# Design_Schematic.net
KiCad netlist of a schematic drawn in EAGLE
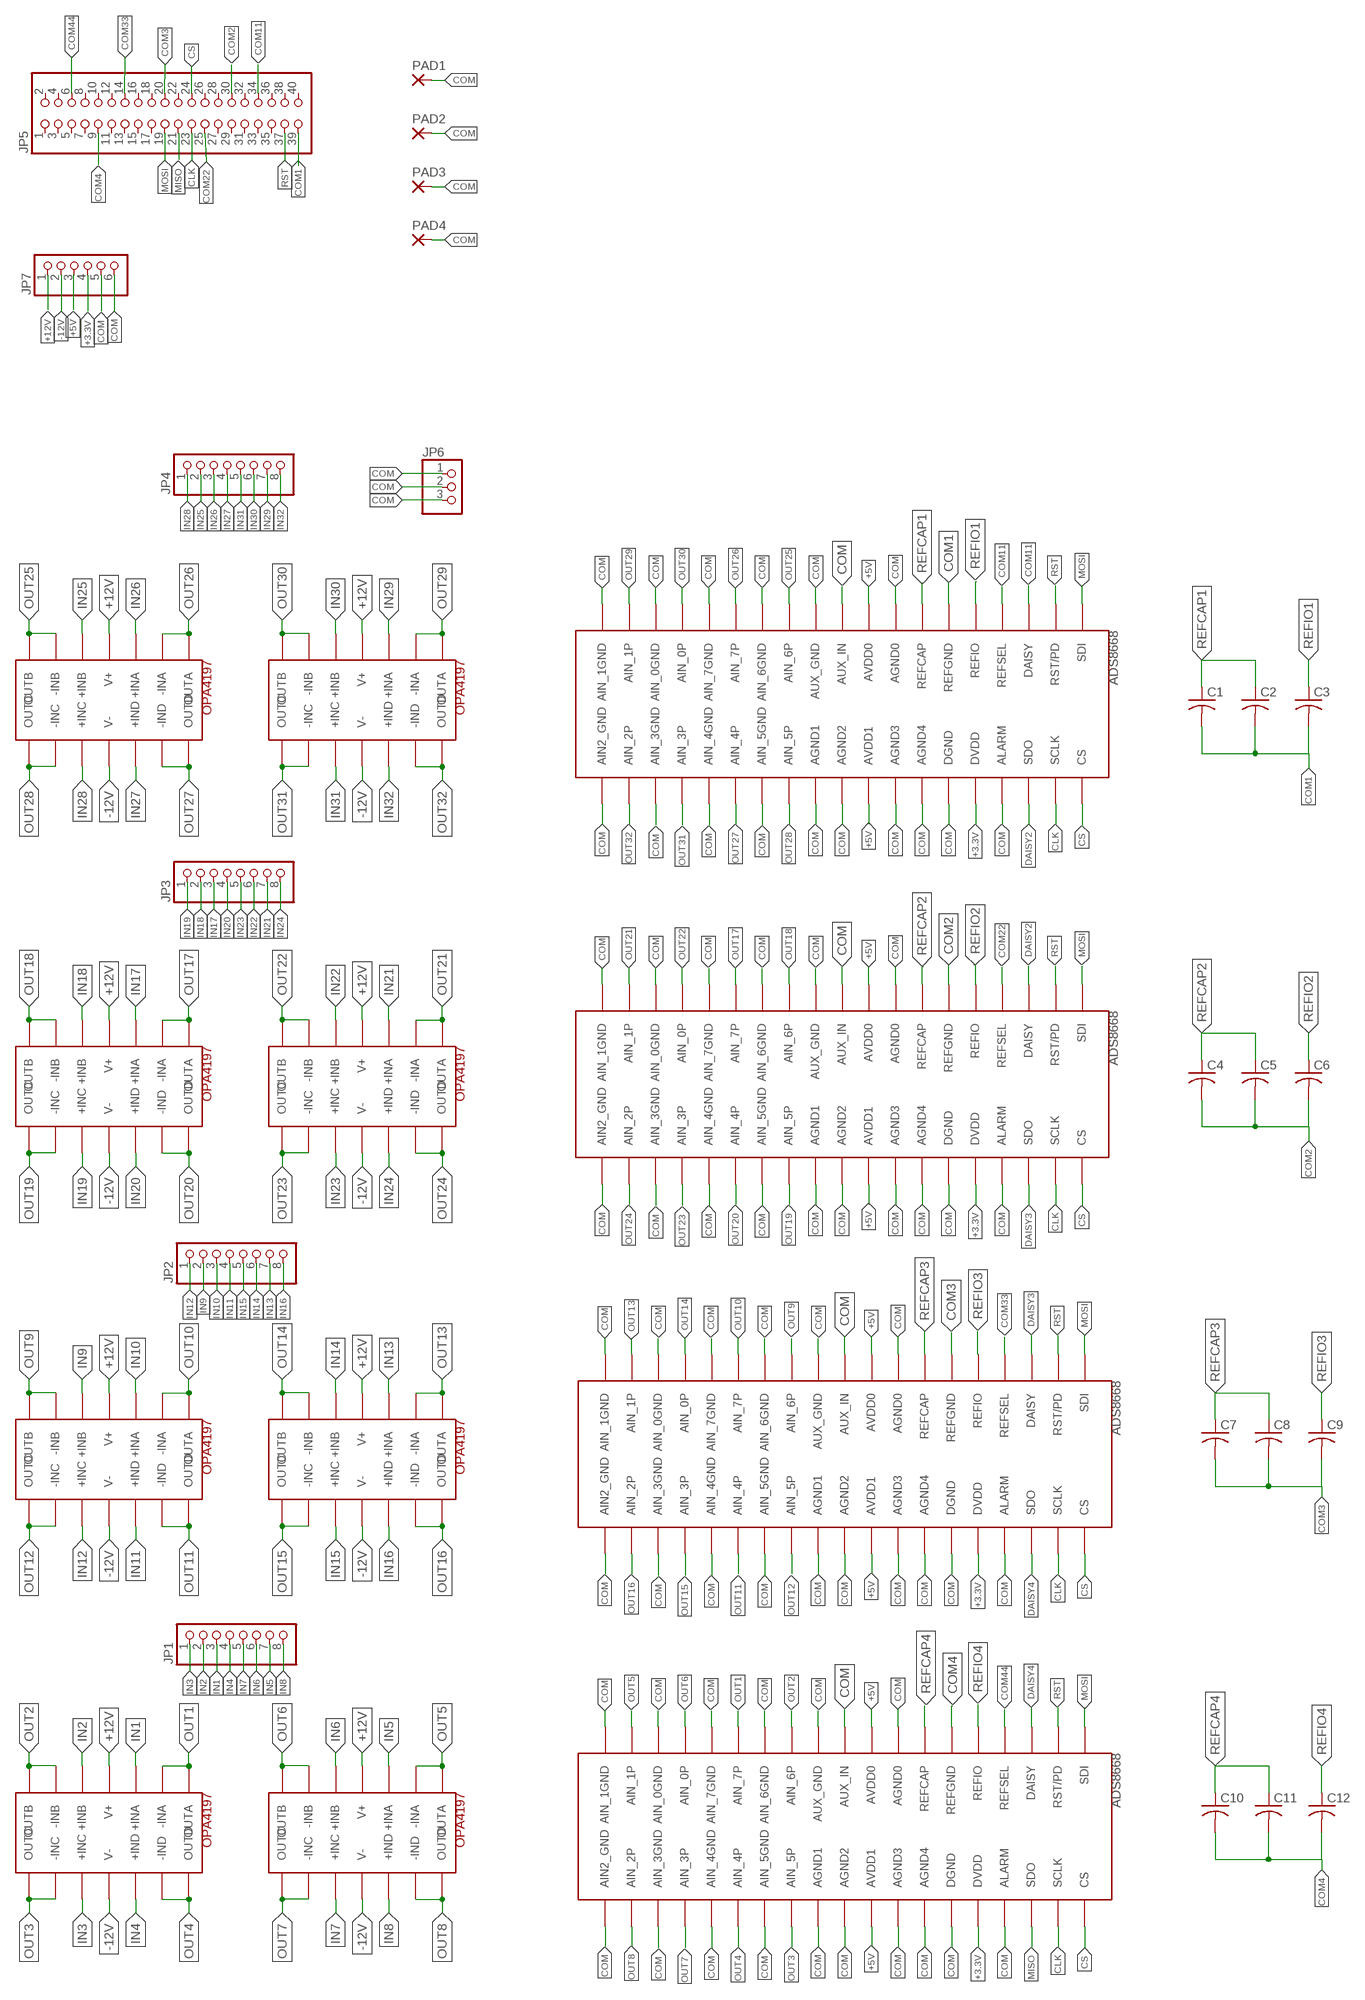
[diagram p0: schematic, sheet 1]

(export (version "E")
  (design (tool "Eeschema 10.0.6"))
  (components
    (comp (ref "ADC1")
      (value "ADS8668")
      (footprint "eagle-import:ADS8668")
      (libsource (lib "eagle-import") (part "ADS8668"))
    )
    (comp (ref "ADC2")
      (value "ADS8668")
      (footprint "eagle-import:ADS8668")
      (libsource (lib "eagle-import") (part "ADS8668"))
    )
    (comp (ref "ADC3")
      (value "ADS8668")
      (footprint "eagle-import:ADS8668")
      (libsource (lib "eagle-import") (part "ADS8668"))
    )
    (comp (ref "ADC4")
      (value "ADS8668")
      (footprint "eagle-import:ADS8668")
      (libsource (lib "eagle-import") (part "ADS8668"))
    )
    (comp (ref "C1")
      (value "C-US025-030X050")
      (footprint "eagle-import:C025-030X050")
      (libsource (lib "eagle-import") (part "C-US025-030X050"))
    )
    (comp (ref "C2")
      (value "C-US025-030X050")
      (footprint "eagle-import:C025-030X050")
      (libsource (lib "eagle-import") (part "C-US025-030X050"))
    )
    (comp (ref "C3")
      (value "C-US025-030X050")
      (footprint "eagle-import:C025-030X050")
      (libsource (lib "eagle-import") (part "C-US025-030X050"))
    )
    (comp (ref "C4")
      (value "C-US025-030X050")
      (footprint "eagle-import:C025-030X050")
      (libsource (lib "eagle-import") (part "C-US025-030X050"))
    )
    (comp (ref "C5")
      (value "C-US025-030X050")
      (footprint "eagle-import:C025-030X050")
      (libsource (lib "eagle-import") (part "C-US025-030X050"))
    )
    (comp (ref "C6")
      (value "C-US025-030X050")
      (footprint "eagle-import:C025-030X050")
      (libsource (lib "eagle-import") (part "C-US025-030X050"))
    )
    (comp (ref "C7")
      (value "C-US025-030X050")
      (footprint "eagle-import:C025-030X050")
      (libsource (lib "eagle-import") (part "C-US025-030X050"))
    )
    (comp (ref "C8")
      (value "C-US025-030X050")
      (footprint "eagle-import:C025-030X050")
      (libsource (lib "eagle-import") (part "C-US025-030X050"))
    )
    (comp (ref "C9")
      (value "C-US025-030X050")
      (footprint "eagle-import:C025-030X050")
      (libsource (lib "eagle-import") (part "C-US025-030X050"))
    )
    (comp (ref "C10")
      (value "C-US025-030X050")
      (footprint "eagle-import:C025-030X050")
      (libsource (lib "eagle-import") (part "C-US025-030X050"))
    )
    (comp (ref "C11")
      (value "C-US025-030X050")
      (footprint "eagle-import:C025-030X050")
      (libsource (lib "eagle-import") (part "C-US025-030X050"))
    )
    (comp (ref "C12")
      (value "C-US025-030X050")
      (footprint "eagle-import:C025-030X050")
      (libsource (lib "eagle-import") (part "C-US025-030X050"))
    )
    (comp (ref "JP1")
      (value "PINHD-1X8CLEANBIG")
      (footprint "eagle-import:1X08-CLEANBIG")
      (libsource (lib "eagle-import") (part "PINHD-1X8CLEANBIG"))
    )
    (comp (ref "JP2")
      (value "PINHD-1X8CLEANBIG")
      (footprint "eagle-import:1X08-CLEANBIG")
      (libsource (lib "eagle-import") (part "PINHD-1X8CLEANBIG"))
    )
    (comp (ref "JP3")
      (value "PINHD-1X8CLEANBIG")
      (footprint "eagle-import:1X08-CLEANBIG")
      (libsource (lib "eagle-import") (part "PINHD-1X8CLEANBIG"))
    )
    (comp (ref "JP4")
      (value "PINHD-1X8CLEANBIG")
      (footprint "eagle-import:1X08-CLEANBIG")
      (libsource (lib "eagle-import") (part "PINHD-1X8CLEANBIG"))
    )
    (comp (ref "JP5")
      (value "PINHD-2X20")
      (footprint "eagle-import:2X20")
      (libsource (lib "eagle-import") (part "PINHD-2X20"))
    )
    (comp (ref "JP6")
      (value "PINHD-1X3")
      (footprint "eagle-import:1X03")
      (libsource (lib "eagle-import") (part "PINHD-1X3"))
    )
    (comp (ref "JP7")
      (value "PINHD-1X6")
      (footprint "eagle-import:1X06")
      (libsource (lib "eagle-import") (part "PINHD-1X6"))
    )
    (comp (ref "PAD1")
      (value "3,17/1,3")
      (footprint "eagle-import:3,17_1,3")
      (libsource (lib "eagle-import") (part "3,17/1,3"))
    )
    (comp (ref "PAD2")
      (value "3,17/1,3")
      (footprint "eagle-import:3,17_1,3")
      (libsource (lib "eagle-import") (part "3,17/1,3"))
    )
    (comp (ref "PAD3")
      (value "3,17/1,3")
      (footprint "eagle-import:3,17_1,3")
      (libsource (lib "eagle-import") (part "3,17/1,3"))
    )
    (comp (ref "PAD4")
      (value "3,17/1,3")
      (footprint "eagle-import:3,17_1,3")
      (libsource (lib "eagle-import") (part "3,17/1,3"))
    )
    (comp (ref "U$1")
      (value "OPA4197")
      (footprint "eagle-import:OPA4197")
      (libsource (lib "eagle-import") (part "OPA4197"))
    )
    (comp (ref "U$2")
      (value "OPA4197")
      (footprint "eagle-import:OPA4197")
      (libsource (lib "eagle-import") (part "OPA4197"))
    )
    (comp (ref "U$3")
      (value "OPA4197")
      (footprint "eagle-import:OPA4197")
      (libsource (lib "eagle-import") (part "OPA4197"))
    )
    (comp (ref "U$4")
      (value "OPA4197")
      (footprint "eagle-import:OPA4197")
      (libsource (lib "eagle-import") (part "OPA4197"))
    )
    (comp (ref "U$5")
      (value "OPA4197")
      (footprint "eagle-import:OPA4197")
      (libsource (lib "eagle-import") (part "OPA4197"))
    )
    (comp (ref "U$6")
      (value "OPA4197")
      (footprint "eagle-import:OPA4197")
      (libsource (lib "eagle-import") (part "OPA4197"))
    )
    (comp (ref "U$7")
      (value "OPA4197")
      (footprint "eagle-import:OPA4197")
      (libsource (lib "eagle-import") (part "OPA4197"))
    )
    (comp (ref "U$8")
      (value "OPA4197")
      (footprint "eagle-import:OPA4197")
      (libsource (lib "eagle-import") (part "OPA4197"))
    )
  )
  (nets
    (net (code "1") (name "+3.3V") (class "Default")
      (node (ref "ADC1") (pin "DVDD") (pinfunction "DVDD_DVDD") (pintype "bidirectional"))
      (node (ref "ADC2") (pin "DVDD") (pinfunction "DVDD_DVDD") (pintype "bidirectional"))
      (node (ref "ADC3") (pin "DVDD") (pinfunction "DVDD_DVDD") (pintype "bidirectional"))
      (node (ref "ADC4") (pin "DVDD") (pinfunction "DVDD_DVDD") (pintype "bidirectional"))
      (node (ref "JP7") (pin "4") (pinfunction "4_4") (pintype "passive"))
    )
    (net (code "2") (name "+5V") (class "Default")
      (node (ref "ADC1") (pin "AVDD0") (pinfunction "AVDD0_AVDD0") (pintype "bidirectional"))
      (node (ref "ADC1") (pin "AVDD1") (pinfunction "AVDD1_AVDD1") (pintype "bidirectional"))
      (node (ref "ADC2") (pin "AVDD0") (pinfunction "AVDD0_AVDD0") (pintype "bidirectional"))
      (node (ref "ADC2") (pin "AVDD1") (pinfunction "AVDD1_AVDD1") (pintype "bidirectional"))
      (node (ref "ADC3") (pin "AVDD0") (pinfunction "AVDD0_AVDD0") (pintype "bidirectional"))
      (node (ref "ADC3") (pin "AVDD1") (pinfunction "AVDD1_AVDD1") (pintype "bidirectional"))
      (node (ref "ADC4") (pin "AVDD0") (pinfunction "AVDD0_AVDD0") (pintype "bidirectional"))
      (node (ref "ADC4") (pin "AVDD1") (pinfunction "AVDD1_AVDD1") (pintype "bidirectional"))
      (node (ref "JP7") (pin "3") (pinfunction "3_3") (pintype "passive"))
    )
    (net (code "3") (name "+12V") (class "Default")
      (node (ref "JP7") (pin "1") (pinfunction "1_1") (pintype "passive"))
      (node (ref "U$1") (pin "V+") (pinfunction "V+_V+") (pintype "bidirectional"))
      (node (ref "U$2") (pin "V+") (pinfunction "V+_V+") (pintype "bidirectional"))
      (node (ref "U$3") (pin "V+") (pinfunction "V+_V+") (pintype "bidirectional"))
      (node (ref "U$4") (pin "V+") (pinfunction "V+_V+") (pintype "bidirectional"))
      (node (ref "U$5") (pin "V+") (pinfunction "V+_V+") (pintype "bidirectional"))
      (node (ref "U$6") (pin "V+") (pinfunction "V+_V+") (pintype "bidirectional"))
      (node (ref "U$7") (pin "V+") (pinfunction "V+_V+") (pintype "bidirectional"))
      (node (ref "U$8") (pin "V+") (pinfunction "V+_V+") (pintype "bidirectional"))
    )
    (net (code "4") (name "-12V") (class "Default")
      (node (ref "JP7") (pin "2") (pinfunction "2_2") (pintype "passive"))
      (node (ref "U$1") (pin "V-") (pinfunction "V-_V-") (pintype "bidirectional"))
      (node (ref "U$2") (pin "V-") (pinfunction "V-_V-") (pintype "bidirectional"))
      (node (ref "U$3") (pin "V-") (pinfunction "V-_V-") (pintype "bidirectional"))
      (node (ref "U$4") (pin "V-") (pinfunction "V-_V-") (pintype "bidirectional"))
      (node (ref "U$5") (pin "V-") (pinfunction "V-_V-") (pintype "bidirectional"))
      (node (ref "U$6") (pin "V-") (pinfunction "V-_V-") (pintype "bidirectional"))
      (node (ref "U$7") (pin "V-") (pinfunction "V-_V-") (pintype "bidirectional"))
      (node (ref "U$8") (pin "V-") (pinfunction "V-_V-") (pintype "bidirectional"))
    )
    (net (code "5") (name "CLK") (class "Default")
      (node (ref "ADC1") (pin "SCLK") (pinfunction "SCLK_SCLK") (pintype "bidirectional"))
      (node (ref "ADC2") (pin "SCLK") (pinfunction "SCLK_SCLK") (pintype "bidirectional"))
      (node (ref "ADC3") (pin "SCLK") (pinfunction "SCLK_SCLK") (pintype "bidirectional"))
      (node (ref "ADC4") (pin "SCLK") (pinfunction "SCLK_SCLK") (pintype "bidirectional"))
      (node (ref "JP5") (pin "23") (pinfunction "23_23") (pintype "passive"))
    )
    (net (code "6") (name "COM") (class "Default")
      (node (ref "ADC1") (pin "AGND0") (pinfunction "AGND0_AGND0") (pintype "bidirectional"))
      (node (ref "ADC1") (pin "AGND1") (pinfunction "AGND1_AGND1") (pintype "bidirectional"))
      (node (ref "ADC1") (pin "AGND2") (pinfunction "AGND2_AGND2") (pintype "bidirectional"))
      (node (ref "ADC1") (pin "AGND3") (pinfunction "AGND3_AGND3") (pintype "bidirectional"))
      (node (ref "ADC1") (pin "AGND4") (pinfunction "AGND4_AGND4") (pintype "bidirectional"))
      (node (ref "ADC1") (pin "AIN2_GND") (pinfunction "AIN2_GND_AIN2_GND") (pintype "bidirectional"))
      (node (ref "ADC1") (pin "AIN6_GND") (pinfunction "AIN_6GND_AIN6_GND") (pintype "bidirectional"))
      (node (ref "ADC1") (pin "AIN_0GND") (pinfunction "AIN_0GND_AIN_0GND") (pintype "bidirectional"))
      (node (ref "ADC1") (pin "AIN_1GND") (pinfunction "AIN_1GND_AIN_1GND") (pintype "bidirectional"))
      (node (ref "ADC1") (pin "AIN_3GND") (pinfunction "AIN_3GND_AIN_3GND") (pintype "bidirectional"))
      (node (ref "ADC1") (pin "AIN_4GND") (pinfunction "AIN_4GND_AIN_4GND") (pintype "bidirectional"))
      (node (ref "ADC1") (pin "AIN_5GND") (pinfunction "AIN_5GND_AIN_5GND") (pintype "bidirectional"))
      (node (ref "ADC1") (pin "AIN_7GND") (pinfunction "AIN_7GND_AIN_7GND") (pintype "bidirectional"))
      (node (ref "ADC1") (pin "ALARM") (pinfunction "ALARM_ALARM") (pintype "bidirectional"))
      (node (ref "ADC1") (pin "AUX_GND") (pinfunction "AUX_GND_AUX_GND") (pintype "bidirectional"))
      (node (ref "ADC1") (pin "AUX_IN") (pinfunction "AUX_IN_AUX_IN") (pintype "bidirectional"))
      (node (ref "ADC1") (pin "DGND") (pinfunction "DGND_DGND") (pintype "bidirectional"))
      (node (ref "ADC2") (pin "AGND0") (pinfunction "AGND0_AGND0") (pintype "bidirectional"))
      (node (ref "ADC2") (pin "AGND1") (pinfunction "AGND1_AGND1") (pintype "bidirectional"))
      (node (ref "ADC2") (pin "AGND2") (pinfunction "AGND2_AGND2") (pintype "bidirectional"))
      (node (ref "ADC2") (pin "AGND3") (pinfunction "AGND3_AGND3") (pintype "bidirectional"))
      (node (ref "ADC2") (pin "AGND4") (pinfunction "AGND4_AGND4") (pintype "bidirectional"))
      (node (ref "ADC2") (pin "AIN2_GND") (pinfunction "AIN2_GND_AIN2_GND") (pintype "bidirectional"))
      (node (ref "ADC2") (pin "AIN6_GND") (pinfunction "AIN_6GND_AIN6_GND") (pintype "bidirectional"))
      (node (ref "ADC2") (pin "AIN_0GND") (pinfunction "AIN_0GND_AIN_0GND") (pintype "bidirectional"))
      (node (ref "ADC2") (pin "AIN_1GND") (pinfunction "AIN_1GND_AIN_1GND") (pintype "bidirectional"))
      (node (ref "ADC2") (pin "AIN_3GND") (pinfunction "AIN_3GND_AIN_3GND") (pintype "bidirectional"))
      (node (ref "ADC2") (pin "AIN_4GND") (pinfunction "AIN_4GND_AIN_4GND") (pintype "bidirectional"))
      (node (ref "ADC2") (pin "AIN_5GND") (pinfunction "AIN_5GND_AIN_5GND") (pintype "bidirectional"))
      (node (ref "ADC2") (pin "AIN_7GND") (pinfunction "AIN_7GND_AIN_7GND") (pintype "bidirectional"))
      (node (ref "ADC2") (pin "ALARM") (pinfunction "ALARM_ALARM") (pintype "bidirectional"))
      (node (ref "ADC2") (pin "AUX_GND") (pinfunction "AUX_GND_AUX_GND") (pintype "bidirectional"))
      (node (ref "ADC2") (pin "AUX_IN") (pinfunction "AUX_IN_AUX_IN") (pintype "bidirectional"))
      (node (ref "ADC2") (pin "DGND") (pinfunction "DGND_DGND") (pintype "bidirectional"))
      (node (ref "ADC3") (pin "AGND0") (pinfunction "AGND0_AGND0") (pintype "bidirectional"))
      (node (ref "ADC3") (pin "AGND1") (pinfunction "AGND1_AGND1") (pintype "bidirectional"))
      (node (ref "ADC3") (pin "AGND2") (pinfunction "AGND2_AGND2") (pintype "bidirectional"))
      (node (ref "ADC3") (pin "AGND3") (pinfunction "AGND3_AGND3") (pintype "bidirectional"))
      (node (ref "ADC3") (pin "AGND4") (pinfunction "AGND4_AGND4") (pintype "bidirectional"))
      (node (ref "ADC3") (pin "AIN2_GND") (pinfunction "AIN2_GND_AIN2_GND") (pintype "bidirectional"))
      (node (ref "ADC3") (pin "AIN6_GND") (pinfunction "AIN_6GND_AIN6_GND") (pintype "bidirectional"))
      (node (ref "ADC3") (pin "AIN_0GND") (pinfunction "AIN_0GND_AIN_0GND") (pintype "bidirectional"))
      (node (ref "ADC3") (pin "AIN_1GND") (pinfunction "AIN_1GND_AIN_1GND") (pintype "bidirectional"))
      (node (ref "ADC3") (pin "AIN_3GND") (pinfunction "AIN_3GND_AIN_3GND") (pintype "bidirectional"))
      (node (ref "ADC3") (pin "AIN_4GND") (pinfunction "AIN_4GND_AIN_4GND") (pintype "bidirectional"))
      (node (ref "ADC3") (pin "AIN_5GND") (pinfunction "AIN_5GND_AIN_5GND") (pintype "bidirectional"))
      (node (ref "ADC3") (pin "AIN_7GND") (pinfunction "AIN_7GND_AIN_7GND") (pintype "bidirectional"))
      (node (ref "ADC3") (pin "ALARM") (pinfunction "ALARM_ALARM") (pintype "bidirectional"))
      (node (ref "ADC3") (pin "AUX_GND") (pinfunction "AUX_GND_AUX_GND") (pintype "bidirectional"))
      (node (ref "ADC3") (pin "AUX_IN") (pinfunction "AUX_IN_AUX_IN") (pintype "bidirectional"))
      (node (ref "ADC3") (pin "DGND") (pinfunction "DGND_DGND") (pintype "bidirectional"))
      (node (ref "ADC4") (pin "AGND0") (pinfunction "AGND0_AGND0") (pintype "bidirectional"))
      (node (ref "ADC4") (pin "AGND1") (pinfunction "AGND1_AGND1") (pintype "bidirectional"))
      (node (ref "ADC4") (pin "AGND2") (pinfunction "AGND2_AGND2") (pintype "bidirectional"))
      (node (ref "ADC4") (pin "AGND3") (pinfunction "AGND3_AGND3") (pintype "bidirectional"))
      (node (ref "ADC4") (pin "AGND4") (pinfunction "AGND4_AGND4") (pintype "bidirectional"))
      (node (ref "ADC4") (pin "AIN2_GND") (pinfunction "AIN2_GND_AIN2_GND") (pintype "bidirectional"))
      (node (ref "ADC4") (pin "AIN6_GND") (pinfunction "AIN_6GND_AIN6_GND") (pintype "bidirectional"))
      (node (ref "ADC4") (pin "AIN_0GND") (pinfunction "AIN_0GND_AIN_0GND") (pintype "bidirectional"))
      (node (ref "ADC4") (pin "AIN_1GND") (pinfunction "AIN_1GND_AIN_1GND") (pintype "bidirectional"))
      (node (ref "ADC4") (pin "AIN_3GND") (pinfunction "AIN_3GND_AIN_3GND") (pintype "bidirectional"))
      (node (ref "ADC4") (pin "AIN_4GND") (pinfunction "AIN_4GND_AIN_4GND") (pintype "bidirectional"))
      (node (ref "ADC4") (pin "AIN_5GND") (pinfunction "AIN_5GND_AIN_5GND") (pintype "bidirectional"))
      (node (ref "ADC4") (pin "AIN_7GND") (pinfunction "AIN_7GND_AIN_7GND") (pintype "bidirectional"))
      (node (ref "ADC4") (pin "ALARM") (pinfunction "ALARM_ALARM") (pintype "bidirectional"))
      (node (ref "ADC4") (pin "AUX_GND") (pinfunction "AUX_GND_AUX_GND") (pintype "bidirectional"))
      (node (ref "ADC4") (pin "AUX_IN") (pinfunction "AUX_IN_AUX_IN") (pintype "bidirectional"))
      (node (ref "ADC4") (pin "DGND") (pinfunction "DGND_DGND") (pintype "bidirectional"))
      (node (ref "JP6") (pin "1") (pinfunction "1_1") (pintype "passive"))
      (node (ref "JP6") (pin "2") (pinfunction "2_2") (pintype "passive"))
      (node (ref "JP6") (pin "3") (pinfunction "3_3") (pintype "passive"))
      (node (ref "JP7") (pin "5") (pinfunction "5_5") (pintype "passive"))
      (node (ref "JP7") (pin "6") (pinfunction "6_6") (pintype "passive"))
      (node (ref "PAD1") (pin "1") (pinfunction "P_1") (pintype "passive"))
      (node (ref "PAD2") (pin "1") (pinfunction "P_1") (pintype "passive"))
      (node (ref "PAD3") (pin "1") (pinfunction "P_1") (pintype "passive"))
      (node (ref "PAD4") (pin "1") (pinfunction "P_1") (pintype "passive"))
    )
    (net (code "7") (name "COM1") (class "Default")
      (node (ref "ADC4") (pin "REFGND") (pinfunction "REFGND_REFGND") (pintype "bidirectional"))
      (node (ref "C1") (pin "2") (pinfunction "2_2") (pintype "passive"))
      (node (ref "C2") (pin "2") (pinfunction "2_2") (pintype "passive"))
      (node (ref "C3") (pin "2") (pinfunction "2_2") (pintype "passive"))
      (node (ref "JP5") (pin "39") (pinfunction "39_39") (pintype "passive"))
    )
    (net (code "8") (name "COM2") (class "Default")
      (node (ref "ADC1") (pin "REFGND") (pinfunction "REFGND_REFGND") (pintype "bidirectional"))
      (node (ref "C4") (pin "2") (pinfunction "2_2") (pintype "passive"))
      (node (ref "C5") (pin "2") (pinfunction "2_2") (pintype "passive"))
      (node (ref "C6") (pin "2") (pinfunction "2_2") (pintype "passive"))
      (node (ref "JP5") (pin "30") (pinfunction "30_30") (pintype "passive"))
    )
    (net (code "9") (name "COM3") (class "Default")
      (node (ref "ADC2") (pin "REFGND") (pinfunction "REFGND_REFGND") (pintype "bidirectional"))
      (node (ref "C7") (pin "2") (pinfunction "2_2") (pintype "passive"))
      (node (ref "C8") (pin "2") (pinfunction "2_2") (pintype "passive"))
      (node (ref "C9") (pin "2") (pinfunction "2_2") (pintype "passive"))
      (node (ref "JP5") (pin "20") (pinfunction "20_20") (pintype "passive"))
    )
    (net (code "10") (name "COM4") (class "Default")
      (node (ref "ADC3") (pin "REFGND") (pinfunction "REFGND_REFGND") (pintype "bidirectional"))
      (node (ref "C10") (pin "2") (pinfunction "2_2") (pintype "passive"))
      (node (ref "C11") (pin "2") (pinfunction "2_2") (pintype "passive"))
      (node (ref "C12") (pin "2") (pinfunction "2_2") (pintype "passive"))
      (node (ref "JP5") (pin "9") (pinfunction "9_9") (pintype "passive"))
    )
    (net (code "11") (name "COM11") (class "Default")
      (node (ref "ADC4") (pin "DAISY") (pinfunction "DAISY_DAISY") (pintype "bidirectional"))
      (node (ref "ADC4") (pin "REFSEL") (pinfunction "REFSEL_REFSEL") (pintype "bidirectional"))
      (node (ref "JP5") (pin "34") (pinfunction "34_34") (pintype "passive"))
    )
    (net (code "12") (name "COM22") (class "Default")
      (node (ref "ADC1") (pin "REFSEL") (pinfunction "REFSEL_REFSEL") (pintype "bidirectional"))
      (node (ref "JP5") (pin "25") (pinfunction "25_25") (pintype "passive"))
    )
    (net (code "13") (name "COM33") (class "Default")
      (node (ref "ADC2") (pin "REFSEL") (pinfunction "REFSEL_REFSEL") (pintype "bidirectional"))
      (node (ref "JP5") (pin "14") (pinfunction "14_14") (pintype "passive"))
    )
    (net (code "14") (name "COM44") (class "Default")
      (node (ref "ADC3") (pin "REFSEL") (pinfunction "REFSEL_REFSEL") (pintype "bidirectional"))
      (node (ref "JP5") (pin "6") (pinfunction "6_6") (pintype "passive"))
    )
    (net (code "15") (name "CS") (class "Default")
      (node (ref "ADC1") (pin "CS") (pinfunction "CS_CS") (pintype "bidirectional"))
      (node (ref "ADC2") (pin "CS") (pinfunction "CS_CS") (pintype "bidirectional"))
      (node (ref "ADC3") (pin "CS") (pinfunction "CS_CS") (pintype "bidirectional"))
      (node (ref "ADC4") (pin "CS") (pinfunction "CS_CS") (pintype "bidirectional"))
      (node (ref "JP5") (pin "24") (pinfunction "24_24") (pintype "passive"))
    )
    (net (code "16") (name "DAISY2") (class "Default")
      (node (ref "ADC1") (pin "DAISY") (pinfunction "DAISY_DAISY") (pintype "bidirectional"))
      (node (ref "ADC4") (pin "SDO") (pinfunction "SDO_SDO") (pintype "bidirectional"))
    )
    (net (code "17") (name "DAISY3") (class "Default")
      (node (ref "ADC1") (pin "SDO") (pinfunction "SDO_SDO") (pintype "bidirectional"))
      (node (ref "ADC2") (pin "DAISY") (pinfunction "DAISY_DAISY") (pintype "bidirectional"))
    )
    (net (code "18") (name "DAISY4") (class "Default")
      (node (ref "ADC2") (pin "SDO") (pinfunction "SDO_SDO") (pintype "bidirectional"))
      (node (ref "ADC3") (pin "DAISY") (pinfunction "DAISY_DAISY") (pintype "bidirectional"))
    )
    (net (code "19") (name "IN1") (class "Default")
      (node (ref "JP1") (pin "3") (pinfunction "3_3") (pintype "passive"))
      (node (ref "U$5") (pin "+INA") (pinfunction "+INA_+INA") (pintype "bidirectional"))
    )
    (net (code "20") (name "IN2") (class "Default")
      (node (ref "JP1") (pin "2") (pinfunction "2_2") (pintype "passive"))
      (node (ref "U$5") (pin "+INB") (pinfunction "+INB_+INB") (pintype "bidirectional"))
    )
    (net (code "21") (name "IN3") (class "Default")
      (node (ref "JP1") (pin "1") (pinfunction "1_1") (pintype "passive"))
      (node (ref "U$5") (pin "+INC") (pinfunction "+INC_+INC") (pintype "bidirectional"))
    )
    (net (code "22") (name "IN4") (class "Default")
      (node (ref "JP1") (pin "4") (pinfunction "4_4") (pintype "passive"))
      (node (ref "U$5") (pin "+IND") (pinfunction "+IND_+IND") (pintype "bidirectional"))
    )
    (net (code "23") (name "IN5") (class "Default")
      (node (ref "JP1") (pin "7") (pinfunction "7_7") (pintype "passive"))
      (node (ref "U$1") (pin "+INA") (pinfunction "+INA_+INA") (pintype "bidirectional"))
    )
    (net (code "24") (name "IN6") (class "Default")
      (node (ref "JP1") (pin "6") (pinfunction "6_6") (pintype "passive"))
      (node (ref "U$1") (pin "+INB") (pinfunction "+INB_+INB") (pintype "bidirectional"))
    )
    (net (code "25") (name "IN7") (class "Default")
      (node (ref "JP1") (pin "5") (pinfunction "5_5") (pintype "passive"))
      (node (ref "U$1") (pin "+INC") (pinfunction "+INC_+INC") (pintype "bidirectional"))
    )
    (net (code "26") (name "IN8") (class "Default")
      (node (ref "JP1") (pin "8") (pinfunction "8_8") (pintype "passive"))
      (node (ref "U$1") (pin "+IND") (pinfunction "+IND_+IND") (pintype "bidirectional"))
    )
    (net (code "27") (name "IN9") (class "Default")
      (node (ref "JP2") (pin "2") (pinfunction "2_2") (pintype "passive"))
      (node (ref "U$2") (pin "+INB") (pinfunction "+INB_+INB") (pintype "bidirectional"))
    )
    (net (code "28") (name "IN10") (class "Default")
      (node (ref "JP2") (pin "3") (pinfunction "3_3") (pintype "passive"))
      (node (ref "U$2") (pin "+INA") (pinfunction "+INA_+INA") (pintype "bidirectional"))
    )
    (net (code "29") (name "IN11") (class "Default")
      (node (ref "JP2") (pin "4") (pinfunction "4_4") (pintype "passive"))
      (node (ref "U$2") (pin "+IND") (pinfunction "+IND_+IND") (pintype "bidirectional"))
    )
    (net (code "30") (name "IN12") (class "Default")
      (node (ref "JP2") (pin "1") (pinfunction "1_1") (pintype "passive"))
      (node (ref "U$2") (pin "+INC") (pinfunction "+INC_+INC") (pintype "bidirectional"))
    )
    (net (code "31") (name "IN13") (class "Default")
      (node (ref "JP2") (pin "7") (pinfunction "7_7") (pintype "passive"))
      (node (ref "U$3") (pin "+INA") (pinfunction "+INA_+INA") (pintype "bidirectional"))
    )
    (net (code "32") (name "IN14") (class "Default")
      (node (ref "JP2") (pin "6") (pinfunction "6_6") (pintype "passive"))
      (node (ref "U$3") (pin "+INB") (pinfunction "+INB_+INB") (pintype "bidirectional"))
    )
    (net (code "33") (name "IN15") (class "Default")
      (node (ref "JP2") (pin "5") (pinfunction "5_5") (pintype "passive"))
      (node (ref "U$3") (pin "+INC") (pinfunction "+INC_+INC") (pintype "bidirectional"))
    )
    (net (code "34") (name "IN16") (class "Default")
      (node (ref "JP2") (pin "8") (pinfunction "8_8") (pintype "passive"))
      (node (ref "U$3") (pin "+IND") (pinfunction "+IND_+IND") (pintype "bidirectional"))
    )
    (net (code "35") (name "IN17") (class "Default")
      (node (ref "JP3") (pin "3") (pinfunction "3_3") (pintype "passive"))
      (node (ref "U$4") (pin "+INA") (pinfunction "+INA_+INA") (pintype "bidirectional"))
    )
    (net (code "36") (name "IN18") (class "Default")
      (node (ref "JP3") (pin "2") (pinfunction "2_2") (pintype "passive"))
      (node (ref "U$4") (pin "+INB") (pinfunction "+INB_+INB") (pintype "bidirectional"))
    )
    (net (code "37") (name "IN19") (class "Default")
      (node (ref "JP3") (pin "1") (pinfunction "1_1") (pintype "passive"))
      (node (ref "U$4") (pin "+INC") (pinfunction "+INC_+INC") (pintype "bidirectional"))
    )
    (net (code "38") (name "IN20") (class "Default")
      (node (ref "JP3") (pin "4") (pinfunction "4_4") (pintype "passive"))
      (node (ref "U$4") (pin "+IND") (pinfunction "+IND_+IND") (pintype "bidirectional"))
    )
    (net (code "39") (name "IN21") (class "Default")
      (node (ref "JP3") (pin "7") (pinfunction "7_7") (pintype "passive"))
      (node (ref "U$6") (pin "+INA") (pinfunction "+INA_+INA") (pintype "bidirectional"))
    )
    (net (code "40") (name "IN22") (class "Default")
      (node (ref "JP3") (pin "6") (pinfunction "6_6") (pintype "passive"))
      (node (ref "U$6") (pin "+INB") (pinfunction "+INB_+INB") (pintype "bidirectional"))
    )
    (net (code "41") (name "IN23") (class "Default")
      (node (ref "JP3") (pin "5") (pinfunction "5_5") (pintype "passive"))
      (node (ref "U$6") (pin "+INC") (pinfunction "+INC_+INC") (pintype "bidirectional"))
    )
    (net (code "42") (name "IN24") (class "Default")
      (node (ref "JP3") (pin "8") (pinfunction "8_8") (pintype "passive"))
      (node (ref "U$6") (pin "+IND") (pinfunction "+IND_+IND") (pintype "bidirectional"))
    )
    (net (code "43") (name "IN25") (class "Default")
      (node (ref "JP4") (pin "2") (pinfunction "2_2") (pintype "passive"))
      (node (ref "U$7") (pin "+INB") (pinfunction "+INB_+INB") (pintype "bidirectional"))
    )
    (net (code "44") (name "IN26") (class "Default")
      (node (ref "JP4") (pin "3") (pinfunction "3_3") (pintype "passive"))
      (node (ref "U$7") (pin "+INA") (pinfunction "+INA_+INA") (pintype "bidirectional"))
    )
    (net (code "45") (name "IN27") (class "Default")
      (node (ref "JP4") (pin "4") (pinfunction "4_4") (pintype "passive"))
      (node (ref "U$7") (pin "+IND") (pinfunction "+IND_+IND") (pintype "bidirectional"))
    )
    (net (code "46") (name "IN28") (class "Default")
      (node (ref "JP4") (pin "1") (pinfunction "1_1") (pintype "passive"))
      (node (ref "U$7") (pin "+INC") (pinfunction "+INC_+INC") (pintype "bidirectional"))
    )
    (net (code "47") (name "IN29") (class "Default")
      (node (ref "JP4") (pin "7") (pinfunction "7_7") (pintype "passive"))
      (node (ref "U$8") (pin "+INA") (pinfunction "+INA_+INA") (pintype "bidirectional"))
    )
    (net (code "48") (name "IN30") (class "Default")
      (node (ref "JP4") (pin "6") (pinfunction "6_6") (pintype "passive"))
      (node (ref "U$8") (pin "+INB") (pinfunction "+INB_+INB") (pintype "bidirectional"))
    )
    (net (code "49") (name "IN31") (class "Default")
      (node (ref "JP4") (pin "5") (pinfunction "5_5") (pintype "passive"))
      (node (ref "U$8") (pin "+INC") (pinfunction "+INC_+INC") (pintype "bidirectional"))
    )
    (net (code "50") (name "IN32") (class "Default")
      (node (ref "JP4") (pin "8") (pinfunction "8_8") (pintype "passive"))
      (node (ref "U$8") (pin "+IND") (pinfunction "+IND_+IND") (pintype "bidirectional"))
    )
    (net (code "51") (name "MISO") (class "Default")
      (node (ref "ADC3") (pin "SDO") (pinfunction "SDO_SDO") (pintype "bidirectional"))
      (node (ref "JP5") (pin "21") (pinfunction "21_21") (pintype "passive"))
    )
    (net (code "52") (name "MOSI") (class "Default")
      (node (ref "ADC1") (pin "SDI") (pinfunction "SDI_SDI") (pintype "bidirectional"))
      (node (ref "ADC2") (pin "SDI") (pinfunction "SDI_SDI") (pintype "bidirectional"))
      (node (ref "ADC3") (pin "SDI") (pinfunction "SDI_SDI") (pintype "bidirectional"))
      (node (ref "ADC4") (pin "SDI") (pinfunction "SDI_SDI") (pintype "bidirectional"))
      (node (ref "JP5") (pin "19") (pinfunction "19_19") (pintype "passive"))
    )
    (net (code "53") (name "OUT1") (class "Default")
      (node (ref "ADC3") (pin "AIN_7P") (pinfunction "AIN_7P_AIN_7P") (pintype "bidirectional"))
      (node (ref "U$5") (pin "-INA") (pinfunction "-INA_-INA") (pintype "bidirectional"))
      (node (ref "U$5") (pin "OUTA") (pinfunction "OUTA_OUTA") (pintype "bidirectional"))
    )
    (net (code "54") (name "OUT2") (class "Default")
      (node (ref "ADC3") (pin "AIN_6P") (pinfunction "AIN_6P_AIN_6P") (pintype "bidirectional"))
      (node (ref "U$5") (pin "-INB") (pinfunction "-INB_-INB") (pintype "bidirectional"))
      (node (ref "U$5") (pin "OUTB") (pinfunction "OUTB_OUTB") (pintype "bidirectional"))
    )
    (net (code "55") (name "OUT3") (class "Default")
      (node (ref "ADC3") (pin "AIN_5P") (pinfunction "AIN_5P_AIN_5P") (pintype "bidirectional"))
      (node (ref "U$5") (pin "-INC") (pinfunction "-INC_-INC") (pintype "bidirectional"))
      (node (ref "U$5") (pin "OUTC") (pinfunction "OUTC_OUTC") (pintype "bidirectional"))
    )
    (net (code "56") (name "OUT4") (class "Default")
      (node (ref "ADC3") (pin "AIN_4P") (pinfunction "AIN_4P_AIN_4P") (pintype "bidirectional"))
      (node (ref "U$5") (pin "-IND") (pinfunction "-IND_-IND") (pintype "bidirectional"))
      (node (ref "U$5") (pin "OUTD") (pinfunction "OUTD_OUTD") (pintype "bidirectional"))
    )
    (net (code "57") (name "OUT5") (class "Default")
      (node (ref "ADC3") (pin "AIN_1P") (pinfunction "AIN_1P_AIN_1P") (pintype "bidirectional"))
      (node (ref "U$1") (pin "-INA") (pinfunction "-INA_-INA") (pintype "bidirectional"))
      (node (ref "U$1") (pin "OUTA") (pinfunction "OUTA_OUTA") (pintype "bidirectional"))
    )
    (net (code "58") (name "OUT6") (class "Default")
      (node (ref "ADC3") (pin "AIN_0P") (pinfunction "AIN_0P_AIN_0P") (pintype "bidirectional"))
      (node (ref "U$1") (pin "-INB") (pinfunction "-INB_-INB") (pintype "bidirectional"))
      (node (ref "U$1") (pin "OUTB") (pinfunction "OUTB_OUTB") (pintype "bidirectional"))
    )
    (net (code "59") (name "OUT7") (class "Default")
      (node (ref "ADC3") (pin "AIN_3P") (pinfunction "AIN_3P_AIN_3P") (pintype "bidirectional"))
      (node (ref "U$1") (pin "-INC") (pinfunction "-INC_-INC") (pintype "bidirectional"))
      (node (ref "U$1") (pin "OUTC") (pinfunction "OUTC_OUTC") (pintype "bidirectional"))
    )
    (net (code "60") (name "OUT8") (class "Default")
      (node (ref "ADC3") (pin "AIN_2P") (pinfunction "AIN_2P_AIN_2P") (pintype "bidirectional"))
      (node (ref "U$1") (pin "-IND") (pinfunction "-IND_-IND") (pintype "bidirectional"))
      (node (ref "U$1") (pin "OUTD") (pinfunction "OUTD_OUTD") (pintype "bidirectional"))
    )
    (net (code "61") (name "OUT9") (class "Default")
      (node (ref "ADC2") (pin "AIN_6P") (pinfunction "AIN_6P_AIN_6P") (pintype "bidirectional"))
      (node (ref "U$2") (pin "-INB") (pinfunction "-INB_-INB") (pintype "bidirectional"))
      (node (ref "U$2") (pin "OUTB") (pinfunction "OUTB_OUTB") (pintype "bidirectional"))
    )
    (net (code "62") (name "OUT10") (class "Default")
      (node (ref "ADC2") (pin "AIN_7P") (pinfunction "AIN_7P_AIN_7P") (pintype "bidirectional"))
      (node (ref "U$2") (pin "-INA") (pinfunction "-INA_-INA") (pintype "bidirectional"))
      (node (ref "U$2") (pin "OUTA") (pinfunction "OUTA_OUTA") (pintype "bidirectional"))
    )
    (net (code "63") (name "OUT11") (class "Default")
      (node (ref "ADC2") (pin "AIN_4P") (pinfunction "AIN_4P_AIN_4P") (pintype "bidirectional"))
      (node (ref "U$2") (pin "-IND") (pinfunction "-IND_-IND") (pintype "bidirectional"))
      (node (ref "U$2") (pin "OUTD") (pinfunction "OUTD_OUTD") (pintype "bidirectional"))
    )
    (net (code "64") (name "OUT12") (class "Default")
      (node (ref "ADC2") (pin "AIN_5P") (pinfunction "AIN_5P_AIN_5P") (pintype "bidirectional"))
      (node (ref "U$2") (pin "-INC") (pinfunction "-INC_-INC") (pintype "bidirectional"))
      (node (ref "U$2") (pin "OUTC") (pinfunction "OUTC_OUTC") (pintype "bidirectional"))
    )
    (net (code "65") (name "OUT13") (class "Default")
      (node (ref "ADC2") (pin "AIN_1P") (pinfunction "AIN_1P_AIN_1P") (pintype "bidirectional"))
      (node (ref "U$3") (pin "-INA") (pinfunction "-INA_-INA") (pintype "bidirectional"))
      (node (ref "U$3") (pin "OUTA") (pinfunction "OUTA_OUTA") (pintype "bidirectional"))
    )
    (net (code "66") (name "OUT14") (class "Default")
      (node (ref "ADC2") (pin "AIN_0P") (pinfunction "AIN_0P_AIN_0P") (pintype "bidirectional"))
      (node (ref "U$3") (pin "-INB") (pinfunction "-INB_-INB") (pintype "bidirectional"))
      (node (ref "U$3") (pin "OUTB") (pinfunction "OUTB_OUTB") (pintype "bidirectional"))
    )
    (net (code "67") (name "OUT15") (class "Default")
      (node (ref "ADC2") (pin "AIN_3P") (pinfunction "AIN_3P_AIN_3P") (pintype "bidirectional"))
      (node (ref "U$3") (pin "-INC") (pinfunction "-INC_-INC") (pintype "bidirectional"))
      (node (ref "U$3") (pin "OUTC") (pinfunction "OUTC_OUTC") (pintype "bidirectional"))
    )
    (net (code "68") (name "OUT16") (class "Default")
      (node (ref "ADC2") (pin "AIN_2P") (pinfunction "AIN_2P_AIN_2P") (pintype "bidirectional"))
      (node (ref "U$3") (pin "-IND") (pinfunction "-IND_-IND") (pintype "bidirectional"))
      (node (ref "U$3") (pin "OUTD") (pinfunction "OUTD_OUTD") (pintype "bidirectional"))
    )
    (net (code "69") (name "OUT17") (class "Default")
      (node (ref "ADC1") (pin "AIN_7P") (pinfunction "AIN_7P_AIN_7P") (pintype "bidirectional"))
      (node (ref "U$4") (pin "-INA") (pinfunction "-INA_-INA") (pintype "bidirectional"))
      (node (ref "U$4") (pin "OUTA") (pinfunction "OUTA_OUTA") (pintype "bidirectional"))
    )
    (net (code "70") (name "OUT18") (class "Default")
      (node (ref "ADC1") (pin "AIN_6P") (pinfunction "AIN_6P_AIN_6P") (pintype "bidirectional"))
      (node (ref "U$4") (pin "-INB") (pinfunction "-INB_-INB") (pintype "bidirectional"))
      (node (ref "U$4") (pin "OUTB") (pinfunction "OUTB_OUTB") (pintype "bidirectional"))
    )
    (net (code "71") (name "OUT19") (class "Default")
      (node (ref "ADC1") (pin "AIN_5P") (pinfunction "AIN_5P_AIN_5P") (pintype "bidirectional"))
      (node (ref "U$4") (pin "-INC") (pinfunction "-INC_-INC") (pintype "bidirectional"))
      (node (ref "U$4") (pin "OUTC") (pinfunction "OUTC_OUTC") (pintype "bidirectional"))
    )
    (net (code "72") (name "OUT20") (class "Default")
      (node (ref "ADC1") (pin "AIN_4P") (pinfunction "AIN_4P_AIN_4P") (pintype "bidirectional"))
      (node (ref "U$4") (pin "-IND") (pinfunction "-IND_-IND") (pintype "bidirectional"))
      (node (ref "U$4") (pin "OUTD") (pinfunction "OUTD_OUTD") (pintype "bidirectional"))
    )
    (net (code "73") (name "OUT21") (class "Default")
      (node (ref "ADC1") (pin "AIN_1P") (pinfunction "AIN_1P_AIN_1P") (pintype "bidirectional"))
      (node (ref "U$6") (pin "-INA") (pinfunction "-INA_-INA") (pintype "bidirectional"))
      (node (ref "U$6") (pin "OUTA") (pinfunction "OUTA_OUTA") (pintype "bidirectional"))
    )
    (net (code "74") (name "OUT22") (class "Default")
      (node (ref "ADC1") (pin "AIN_0P") (pinfunction "AIN_0P_AIN_0P") (pintype "bidirectional"))
      (node (ref "U$6") (pin "-INB") (pinfunction "-INB_-INB") (pintype "bidirectional"))
      (node (ref "U$6") (pin "OUTB") (pinfunction "OUTB_OUTB") (pintype "bidirectional"))
    )
    (net (code "75") (name "OUT23") (class "Default")
      (node (ref "ADC1") (pin "AIN_3P") (pinfunction "AIN_3P_AIN_3P") (pintype "bidirectional"))
      (node (ref "U$6") (pin "-INC") (pinfunction "-INC_-INC") (pintype "bidirectional"))
      (node (ref "U$6") (pin "OUTC") (pinfunction "OUTC_OUTC") (pintype "bidirectional"))
    )
    (net (code "76") (name "OUT24") (class "Default")
      (node (ref "ADC1") (pin "AIN_2P") (pinfunction "AIN_2P_AIN_2P") (pintype "bidirectional"))
      (node (ref "U$6") (pin "-IND") (pinfunction "-IND_-IND") (pintype "bidirectional"))
      (node (ref "U$6") (pin "OUTD") (pinfunction "OUTD_OUTD") (pintype "bidirectional"))
    )
    (net (code "77") (name "OUT25") (class "Default")
      (node (ref "ADC4") (pin "AIN_6P") (pinfunction "AIN_6P_AIN_6P") (pintype "bidirectional"))
      (node (ref "U$7") (pin "-INB") (pinfunction "-INB_-INB") (pintype "bidirectional"))
      (node (ref "U$7") (pin "OUTB") (pinfunction "OUTB_OUTB") (pintype "bidirectional"))
    )
    (net (code "78") (name "OUT26") (class "Default")
      (node (ref "ADC4") (pin "AIN_7P") (pinfunction "AIN_7P_AIN_7P") (pintype "bidirectional"))
      (node (ref "U$7") (pin "-INA") (pinfunction "-INA_-INA") (pintype "bidirectional"))
      (node (ref "U$7") (pin "OUTA") (pinfunction "OUTA_OUTA") (pintype "bidirectional"))
    )
    (net (code "79") (name "OUT27") (class "Default")
      (node (ref "ADC4") (pin "AIN_4P") (pinfunction "AIN_4P_AIN_4P") (pintype "bidirectional"))
      (node (ref "U$7") (pin "-IND") (pinfunction "-IND_-IND") (pintype "bidirectional"))
      (node (ref "U$7") (pin "OUTD") (pinfunction "OUTD_OUTD") (pintype "bidirectional"))
    )
    (net (code "80") (name "OUT28") (class "Default")
      (node (ref "ADC4") (pin "AIN_5P") (pinfunction "AIN_5P_AIN_5P") (pintype "bidirectional"))
      (node (ref "U$7") (pin "-INC") (pinfunction "-INC_-INC") (pintype "bidirectional"))
      (node (ref "U$7") (pin "OUTC") (pinfunction "OUTC_OUTC") (pintype "bidirectional"))
    )
    (net (code "81") (name "OUT29") (class "Default")
      (node (ref "ADC4") (pin "AIN_1P") (pinfunction "AIN_1P_AIN_1P") (pintype "bidirectional"))
      (node (ref "U$8") (pin "-INA") (pinfunction "-INA_-INA") (pintype "bidirectional"))
      (node (ref "U$8") (pin "OUTA") (pinfunction "OUTA_OUTA") (pintype "bidirectional"))
    )
    (net (code "82") (name "OUT30") (class "Default")
      (node (ref "ADC4") (pin "AIN_0P") (pinfunction "AIN_0P_AIN_0P") (pintype "bidirectional"))
      (node (ref "U$8") (pin "-INB") (pinfunction "-INB_-INB") (pintype "bidirectional"))
      (node (ref "U$8") (pin "OUTB") (pinfunction "OUTB_OUTB") (pintype "bidirectional"))
    )
    (net (code "83") (name "OUT31") (class "Default")
      (node (ref "ADC4") (pin "AIN_3P") (pinfunction "AIN_3P_AIN_3P") (pintype "bidirectional"))
      (node (ref "U$8") (pin "-INC") (pinfunction "-INC_-INC") (pintype "bidirectional"))
      (node (ref "U$8") (pin "OUTC") (pinfunction "OUTC_OUTC") (pintype "bidirectional"))
    )
    (net (code "84") (name "OUT32") (class "Default")
      (node (ref "ADC4") (pin "AIN_2P") (pinfunction "AIN_2P_AIN_2P") (pintype "bidirectional"))
      (node (ref "U$8") (pin "-IND") (pinfunction "-IND_-IND") (pintype "bidirectional"))
      (node (ref "U$8") (pin "OUTD") (pinfunction "OUTD_OUTD") (pintype "bidirectional"))
    )
    (net (code "85") (name "REFCAP1") (class "Default")
      (node (ref "ADC4") (pin "REFCAP") (pinfunction "REFCAP_REFCAP") (pintype "bidirectional"))
      (node (ref "C1") (pin "1") (pinfunction "1_1") (pintype "passive"))
      (node (ref "C2") (pin "1") (pinfunction "1_1") (pintype "passive"))
    )
    (net (code "86") (name "REFCAP2") (class "Default")
      (node (ref "ADC1") (pin "REFCAP") (pinfunction "REFCAP_REFCAP") (pintype "bidirectional"))
      (node (ref "C4") (pin "1") (pinfunction "1_1") (pintype "passive"))
      (node (ref "C5") (pin "1") (pinfunction "1_1") (pintype "passive"))
    )
    (net (code "87") (name "REFCAP3") (class "Default")
      (node (ref "ADC2") (pin "REFCAP") (pinfunction "REFCAP_REFCAP") (pintype "bidirectional"))
      (node (ref "C7") (pin "1") (pinfunction "1_1") (pintype "passive"))
      (node (ref "C8") (pin "1") (pinfunction "1_1") (pintype "passive"))
    )
    (net (code "88") (name "REFCAP4") (class "Default")
      (node (ref "ADC3") (pin "REFCAP") (pinfunction "REFCAP_REFCAP") (pintype "bidirectional"))
      (node (ref "C10") (pin "1") (pinfunction "1_1") (pintype "passive"))
      (node (ref "C11") (pin "1") (pinfunction "1_1") (pintype "passive"))
    )
    (net (code "89") (name "REFIO1") (class "Default")
      (node (ref "ADC4") (pin "REFIO") (pinfunction "REFIO_REFIO") (pintype "bidirectional"))
      (node (ref "C3") (pin "1") (pinfunction "1_1") (pintype "passive"))
    )
    (net (code "90") (name "REFIO2") (class "Default")
      (node (ref "ADC1") (pin "REFIO") (pinfunction "REFIO_REFIO") (pintype "bidirectional"))
      (node (ref "C6") (pin "1") (pinfunction "1_1") (pintype "passive"))
    )
    (net (code "91") (name "REFIO3") (class "Default")
      (node (ref "ADC2") (pin "REFIO") (pinfunction "REFIO_REFIO") (pintype "bidirectional"))
      (node (ref "C9") (pin "1") (pinfunction "1_1") (pintype "passive"))
    )
    (net (code "92") (name "REFIO4") (class "Default")
      (node (ref "ADC3") (pin "REFIO") (pinfunction "REFIO_REFIO") (pintype "bidirectional"))
      (node (ref "C12") (pin "1") (pinfunction "1_1") (pintype "passive"))
    )
    (net (code "93") (name "RST") (class "Default")
      (node (ref "ADC1") (pin "RST/PD") (pinfunction "RST/PD_RST/PD") (pintype "bidirectional"))
      (node (ref "ADC2") (pin "RST/PD") (pinfunction "RST/PD_RST/PD") (pintype "bidirectional"))
      (node (ref "ADC3") (pin "RST/PD") (pinfunction "RST/PD_RST/PD") (pintype "bidirectional"))
      (node (ref "ADC4") (pin "RST/PD") (pinfunction "RST/PD_RST/PD") (pintype "bidirectional"))
      (node (ref "JP5") (pin "37") (pinfunction "37_37") (pintype "passive"))
    )
    (net (code "94") (name "unconnected-(JP5-Pad1)") (class "Default")
      (node (ref "JP5") (pin "1") (pinfunction "1_1") (pintype "passive"))
    )
    (net (code "95") (name "unconnected-(JP5-Pad2)") (class "Default")
      (node (ref "JP5") (pin "2") (pinfunction "2_2") (pintype "passive"))
    )
    (net (code "96") (name "unconnected-(JP5-Pad3)") (class "Default")
      (node (ref "JP5") (pin "3") (pinfunction "3_3") (pintype "passive"))
    )
    (net (code "97") (name "unconnected-(JP5-Pad4)") (class "Default")
      (node (ref "JP5") (pin "4") (pinfunction "4_4") (pintype "passive"))
    )
    (net (code "98") (name "unconnected-(JP5-Pad5)") (class "Default")
      (node (ref "JP5") (pin "5") (pinfunction "5_5") (pintype "passive"))
    )
    (net (code "99") (name "unconnected-(JP5-Pad7)") (class "Default")
      (node (ref "JP5") (pin "7") (pinfunction "7_7") (pintype "passive"))
    )
    (net (code "100") (name "unconnected-(JP5-Pad8)") (class "Default")
      (node (ref "JP5") (pin "8") (pinfunction "8_8") (pintype "passive"))
    )
    (net (code "101") (name "unconnected-(JP5-Pad10)") (class "Default")
      (node (ref "JP5") (pin "10") (pinfunction "10_10") (pintype "passive"))
    )
    (net (code "102") (name "unconnected-(JP5-Pad11)") (class "Default")
      (node (ref "JP5") (pin "11") (pinfunction "11_11") (pintype "passive"))
    )
    (net (code "103") (name "unconnected-(JP5-Pad12)") (class "Default")
      (node (ref "JP5") (pin "12") (pinfunction "12_12") (pintype "passive"))
    )
    (net (code "104") (name "unconnected-(JP5-Pad13)") (class "Default")
      (node (ref "JP5") (pin "13") (pinfunction "13_13") (pintype "passive"))
    )
    (net (code "105") (name "unconnected-(JP5-Pad15)") (class "Default")
      (node (ref "JP5") (pin "15") (pinfunction "15_15") (pintype "passive"))
    )
    (net (code "106") (name "unconnected-(JP5-Pad16)") (class "Default")
      (node (ref "JP5") (pin "16") (pinfunction "16_16") (pintype "passive"))
    )
    (net (code "107") (name "unconnected-(JP5-Pad17)") (class "Default")
      (node (ref "JP5") (pin "17") (pinfunction "17_17") (pintype "passive"))
    )
    (net (code "108") (name "unconnected-(JP5-Pad18)") (class "Default")
      (node (ref "JP5") (pin "18") (pinfunction "18_18") (pintype "passive"))
    )
    (net (code "109") (name "unconnected-(JP5-Pad22)") (class "Default")
      (node (ref "JP5") (pin "22") (pinfunction "22_22") (pintype "passive"))
    )
    (net (code "110") (name "unconnected-(JP5-Pad26)") (class "Default")
      (node (ref "JP5") (pin "26") (pinfunction "26_26") (pintype "passive"))
    )
    (net (code "111") (name "unconnected-(JP5-Pad27)") (class "Default")
      (node (ref "JP5") (pin "27") (pinfunction "27_27") (pintype "passive"))
    )
    (net (code "112") (name "unconnected-(JP5-Pad28)") (class "Default")
      (node (ref "JP5") (pin "28") (pinfunction "28_28") (pintype "passive"))
    )
    (net (code "113") (name "unconnected-(JP5-Pad29)") (class "Default")
      (node (ref "JP5") (pin "29") (pinfunction "29_29") (pintype "passive"))
    )
    (net (code "114") (name "unconnected-(JP5-Pad31)") (class "Default")
      (node (ref "JP5") (pin "31") (pinfunction "31_31") (pintype "passive"))
    )
    (net (code "115") (name "unconnected-(JP5-Pad32)") (class "Default")
      (node (ref "JP5") (pin "32") (pinfunction "32_32") (pintype "passive"))
    )
    (net (code "116") (name "unconnected-(JP5-Pad33)") (class "Default")
      (node (ref "JP5") (pin "33") (pinfunction "33_33") (pintype "passive"))
    )
    (net (code "117") (name "unconnected-(JP5-Pad35)") (class "Default")
      (node (ref "JP5") (pin "35") (pinfunction "35_35") (pintype "passive"))
    )
    (net (code "118") (name "unconnected-(JP5-Pad36)") (class "Default")
      (node (ref "JP5") (pin "36") (pinfunction "36_36") (pintype "passive"))
    )
    (net (code "119") (name "unconnected-(JP5-Pad38)") (class "Default")
      (node (ref "JP5") (pin "38") (pinfunction "38_38") (pintype "passive"))
    )
    (net (code "120") (name "unconnected-(JP5-Pad40)") (class "Default")
      (node (ref "JP5") (pin "40") (pinfunction "40_40") (pintype "passive"))
    )
  )
)
